# SHT1x.net
KiCad netlist of a schematic drawn in Altium Designer
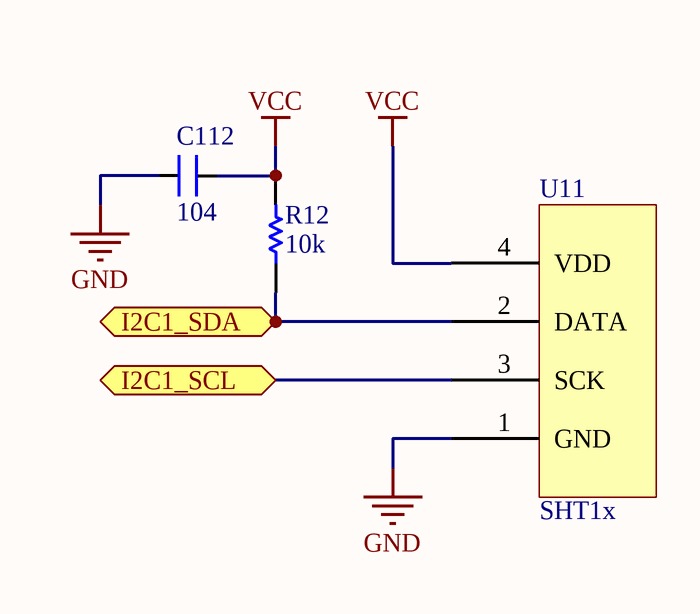
[diagram p0: SHT1x.SchDoc]

(export (version "E")
  (design (tool "Eeschema 10.0.6"))
  (components
    (comp (ref "C112")
      (value "104")
      (footprint "CAPC1608N")
      (fields (field (name "Comment") "CAP NP"))
      (libsource (lib "Tuan") (part "CAP NP"))
    )
    (comp (ref "R12")
      (value "10k")
      (footprint "RESC2012N_F")
      (fields (field (name "Comment") "Res"))
      (libsource (lib "Tuan") (part "Res"))
    )
    (comp (ref "U11") (value "SHT1x") (footprint "SHT1x") (libsource (lib "Tuan") (part "SHT1x")))
  )
  (nets
    (net (code "1") (name "/I2C1_SCL") (class "Default")
      (node (ref "U11") (pin "3") (pinfunction "SCK_3") (pintype "passive"))
    )
    (net (code "2") (name "/I2C1_SDA") (class "Default")
      (node (ref "R12") (pin "1") (pinfunction "1_1") (pintype "passive"))
      (node (ref "U11") (pin "2") (pinfunction "DATA_2") (pintype "passive"))
    )
    (net (code "3") (name "GND") (class "Default")
      (node (ref "C112") (pin "2") (pinfunction "2_2") (pintype "passive"))
      (node (ref "U11") (pin "1") (pinfunction "GND_1") (pintype "passive"))
    )
    (net (code "4") (name "VCC") (class "Default")
      (node (ref "C112") (pin "1") (pinfunction "1_1") (pintype "passive"))
      (node (ref "R12") (pin "2") (pinfunction "2_2") (pintype "passive"))
      (node (ref "U11") (pin "4") (pinfunction "VDD_4") (pintype "passive"))
    )
  )
)
